# higs_bc_eee.net
KiCad netlist of a schematic drawn in EAGLE
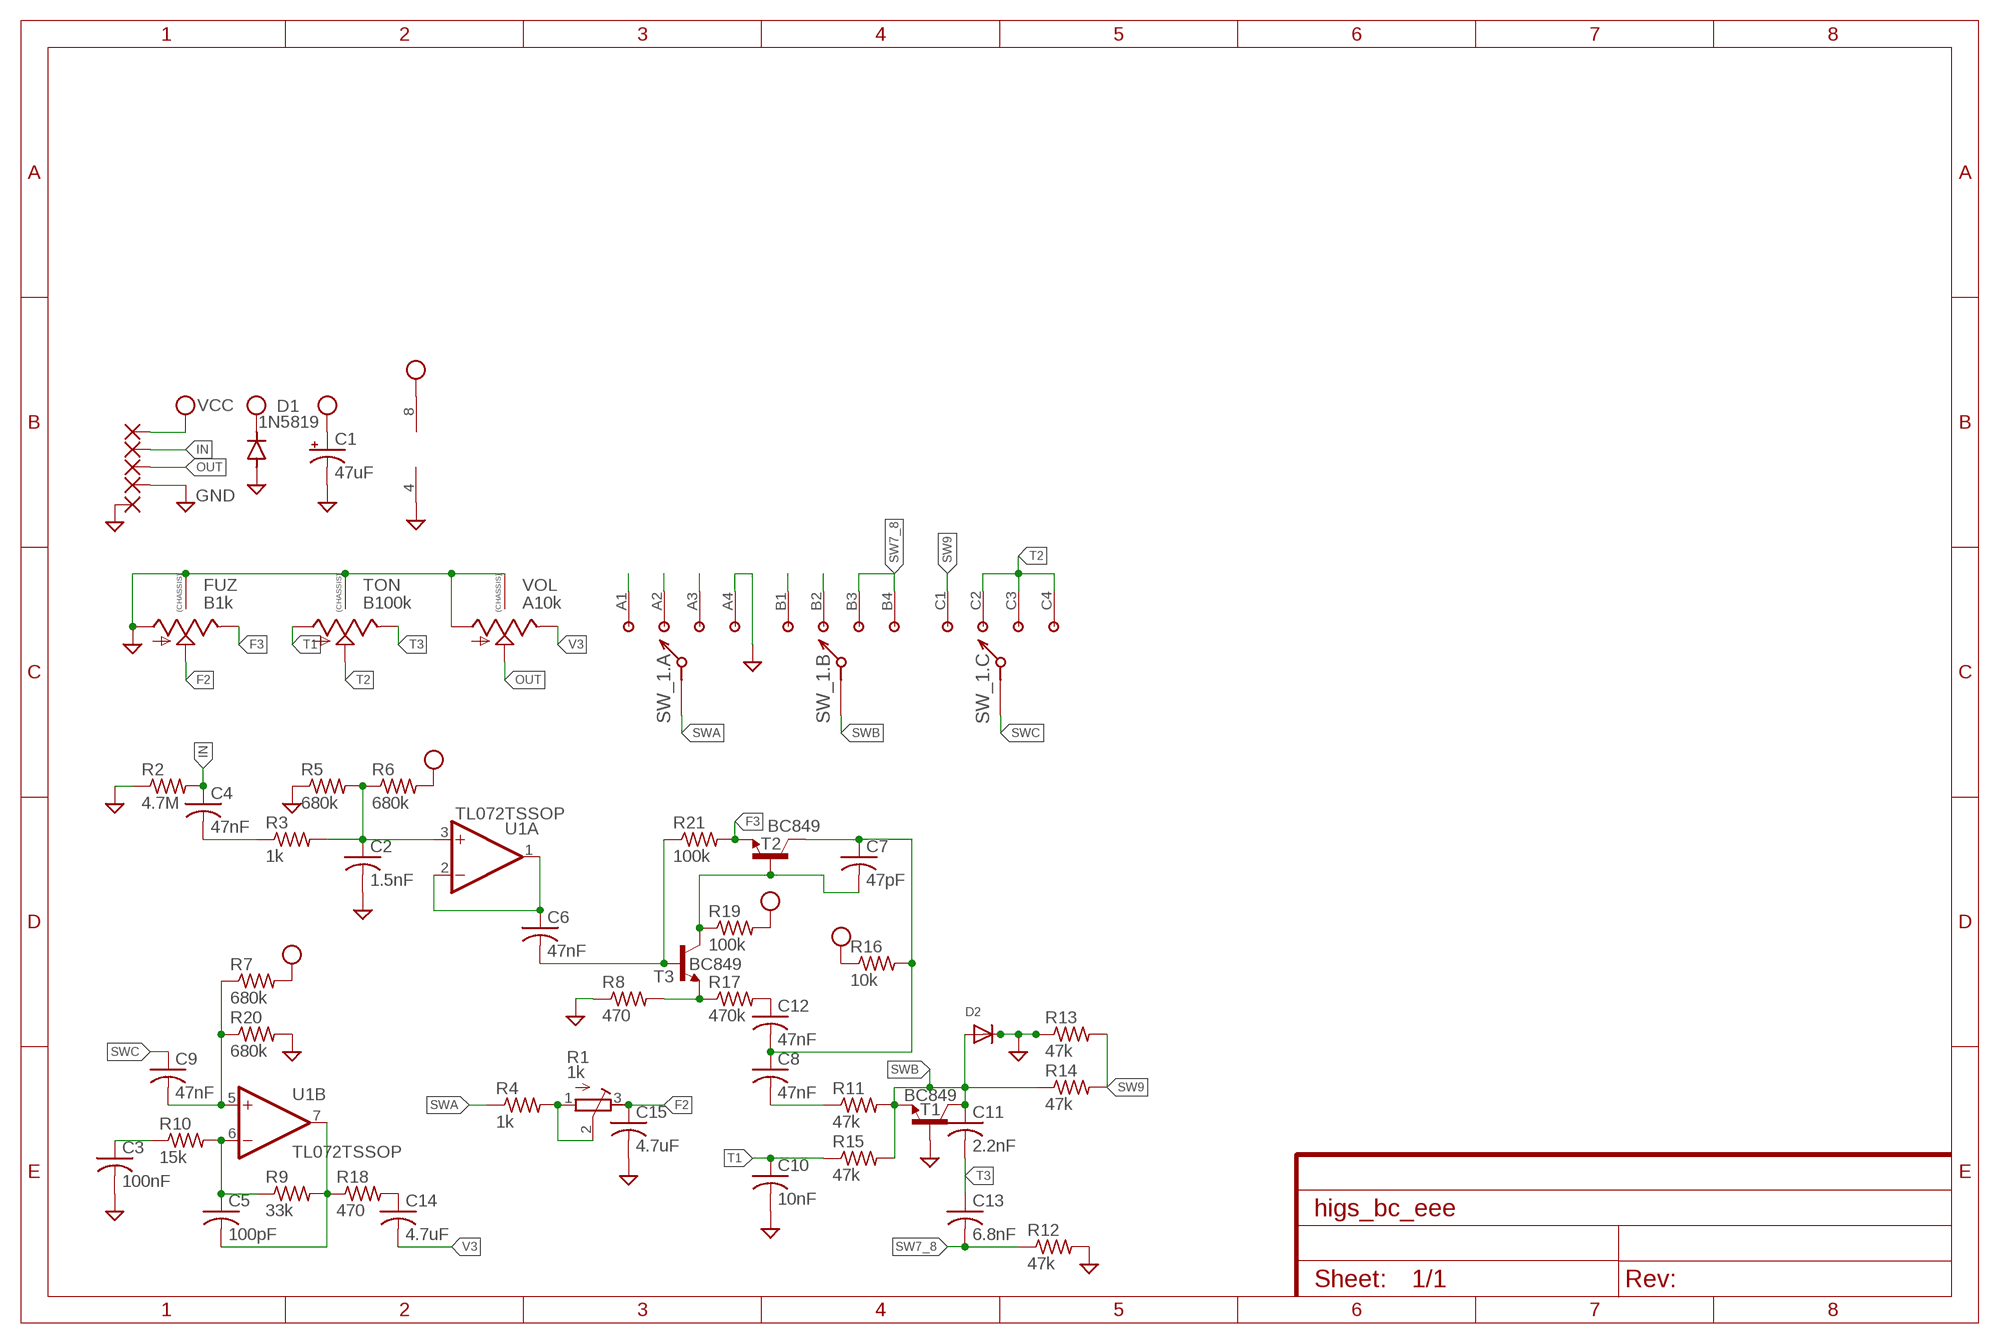
[diagram p0: schematic, sheet 1]

(export (version "E")
  (design (tool "Eeschema 10.0.6"))
  (components
    (comp (ref "C1")
      (value "47uF")
      (footprint "eagle-import:CPOL-RADIAL-2.5MM-6.5MM")
      (libsource (lib "eagle-import") (part "100UF-POLAR-RADIAL-2.5MM-25V-20%"))
    )
    (comp (ref "C2")
      (value "1.5nF")
      (footprint "eagle-import:C0603")
      (libsource (lib "eagle-import") (part "C-USC0603"))
    )
    (comp (ref "C3")
      (value "100nF")
      (footprint "eagle-import:C0603")
      (libsource (lib "eagle-import") (part "C-USC0603"))
    )
    (comp (ref "C4")
      (value "47nF")
      (footprint "eagle-import:C0603")
      (libsource (lib "eagle-import") (part "C-USC0603"))
    )
    (comp (ref "C5")
      (value "100pF")
      (footprint "eagle-import:C0603")
      (libsource (lib "eagle-import") (part "C-USC0603"))
    )
    (comp (ref "C6")
      (value "47nF")
      (footprint "eagle-import:C0603")
      (libsource (lib "eagle-import") (part "C-USC0603"))
    )
    (comp (ref "C7")
      (value "47pF")
      (footprint "eagle-import:C0603")
      (libsource (lib "eagle-import") (part "C-USC0603"))
    )
    (comp (ref "C8")
      (value "47nF")
      (footprint "eagle-import:C0603")
      (libsource (lib "eagle-import") (part "C-USC0603"))
    )
    (comp (ref "C9")
      (value "47nF")
      (footprint "eagle-import:C0603")
      (libsource (lib "eagle-import") (part "C-USC0603"))
    )
    (comp (ref "C10")
      (value "10nF")
      (footprint "eagle-import:C0603")
      (libsource (lib "eagle-import") (part "C-USC0603"))
    )
    (comp (ref "C11")
      (value "2.2nF")
      (footprint "eagle-import:C0603")
      (libsource (lib "eagle-import") (part "C-USC0603"))
    )
    (comp (ref "C12")
      (value "47nF")
      (footprint "eagle-import:C0603")
      (libsource (lib "eagle-import") (part "C-USC0603"))
    )
    (comp (ref "C13")
      (value "6.8nF")
      (footprint "eagle-import:C0603")
      (libsource (lib "eagle-import") (part "C-USC0603"))
    )
    (comp (ref "C14")
      (value "4.7uF")
      (footprint "eagle-import:C1206")
      (libsource (lib "eagle-import") (part "C-USC1206"))
    )
    (comp (ref "C15")
      (value "4.7uF")
      (footprint "eagle-import:C1206")
      (libsource (lib "eagle-import") (part "C-USC1206"))
    )
    (comp (ref "D1")
      (value "1N5819")
      (footprint "eagle-import:SOD123")
      (libsource (lib "eagle-import") (part "DIODE-SOD123"))
    )
    (comp (ref "D2")
      (value "DIODESOD-123")
      (footprint "eagle-import:SOD-123")
      (libsource (lib "eagle-import") (part "DIODESOD-123"))
    )
    (comp (ref "FUZ")
      (value "B1k")
      (footprint "eagle-import:9MM_SNAP-IN_POT")
      (libsource (lib "eagle-import") (part "9MM_SNAP-IN_POT_CHASSIS"))
    )
    (comp (ref "PAD1")
      (value "1,6/0,8")
      (footprint "eagle-import:1,6_0,8")
      (libsource (lib "eagle-import") (part "1,6/0,8"))
    )
    (comp (ref "PAD2")
      (value "1,6/0,8")
      (footprint "eagle-import:1,6_0,8")
      (libsource (lib "eagle-import") (part "1,6/0,8"))
    )
    (comp (ref "PAD3")
      (value "1,6/0,8")
      (footprint "eagle-import:1,6_0,8")
      (libsource (lib "eagle-import") (part "1,6/0,8"))
    )
    (comp (ref "PAD4")
      (value "1,6/0,8")
      (footprint "eagle-import:1,6_0,8")
      (libsource (lib "eagle-import") (part "1,6/0,8"))
    )
    (comp (ref "PAD5")
      (value "1,6/0,8")
      (footprint "eagle-import:1,6_0,8")
      (libsource (lib "eagle-import") (part "1,6/0,8"))
    )
    (comp (ref "R1")
      (value "1k")
      (footprint "eagle-import:RTRIM3224W")
      (libsource (lib "eagle-import") (part "R-TRIMM3224W"))
    )
    (comp (ref "R2")
      (value "4.7M")
      (footprint "eagle-import:R0603")
      (libsource (lib "eagle-import") (part "R-US_R0603"))
    )
    (comp (ref "R3")
      (value "1k")
      (footprint "eagle-import:R0603")
      (libsource (lib "eagle-import") (part "R-US_R0603"))
    )
    (comp (ref "R4")
      (value "1k")
      (footprint "eagle-import:R0603")
      (libsource (lib "eagle-import") (part "R-US_R0603"))
    )
    (comp (ref "R5")
      (value "680k")
      (footprint "eagle-import:R0603")
      (libsource (lib "eagle-import") (part "R-US_R0603"))
    )
    (comp (ref "R6")
      (value "680k")
      (footprint "eagle-import:R0603")
      (libsource (lib "eagle-import") (part "R-US_R0603"))
    )
    (comp (ref "R7")
      (value "680k")
      (footprint "eagle-import:R0603")
      (libsource (lib "eagle-import") (part "R-US_R0603"))
    )
    (comp (ref "R8")
      (value "470")
      (footprint "eagle-import:R0603")
      (libsource (lib "eagle-import") (part "R-US_R0603"))
    )
    (comp (ref "R9")
      (value "33k")
      (footprint "eagle-import:R0603")
      (libsource (lib "eagle-import") (part "R-US_R0603"))
    )
    (comp (ref "R10")
      (value "15k")
      (footprint "eagle-import:R0603")
      (libsource (lib "eagle-import") (part "R-US_R0603"))
    )
    (comp (ref "R11")
      (value "47k")
      (footprint "eagle-import:R0603")
      (libsource (lib "eagle-import") (part "R-US_R0603"))
    )
    (comp (ref "R12")
      (value "47k")
      (footprint "eagle-import:R0603")
      (libsource (lib "eagle-import") (part "R-US_R0603"))
    )
    (comp (ref "R13")
      (value "47k")
      (footprint "eagle-import:R0603")
      (libsource (lib "eagle-import") (part "R-US_R0603"))
    )
    (comp (ref "R14")
      (value "47k")
      (footprint "eagle-import:R0603")
      (libsource (lib "eagle-import") (part "R-US_R0603"))
    )
    (comp (ref "R15")
      (value "47k")
      (footprint "eagle-import:R0603")
      (libsource (lib "eagle-import") (part "R-US_R0603"))
    )
    (comp (ref "R16")
      (value "10k")
      (footprint "eagle-import:R0603")
      (libsource (lib "eagle-import") (part "R-US_R0603"))
    )
    (comp (ref "R17")
      (value "470k")
      (footprint "eagle-import:R0603")
      (libsource (lib "eagle-import") (part "R-US_R0603"))
    )
    (comp (ref "R18")
      (value "470")
      (footprint "eagle-import:R0603")
      (libsource (lib "eagle-import") (part "R-US_R0603"))
    )
    (comp (ref "R19")
      (value "100k")
      (footprint "eagle-import:R0603")
      (libsource (lib "eagle-import") (part "R-US_R0603"))
    )
    (comp (ref "R20")
      (value "680k")
      (footprint "eagle-import:R0603")
      (libsource (lib "eagle-import") (part "R-US_R0603"))
    )
    (comp (ref "R21")
      (value "100k")
      (footprint "eagle-import:R0603")
      (libsource (lib "eagle-import") (part "R-US_R0603"))
    )
    (comp (ref "SW_1")
      (value "3P4T")
      (footprint "eagle-import:3P4T")
      (libsource (lib "eagle-import") (part "3P4T"))
    )
    (comp (ref "T1")
      (value "BC849")
      (footprint "eagle-import:SOT23-BEC")
      (libsource (lib "eagle-import") (part "-NPN-SOT23-BECBC849"))
    )
    (comp (ref "T2")
      (value "BC849")
      (footprint "eagle-import:SOT23-BEC")
      (libsource (lib "eagle-import") (part "-NPN-SOT23-BECBC849"))
    )
    (comp (ref "T3")
      (value "BC849")
      (footprint "eagle-import:SOT23-BEC")
      (libsource (lib "eagle-import") (part "-NPN-SOT23-BECBC849"))
    )
    (comp (ref "TON")
      (value "B100k")
      (footprint "eagle-import:9MM_SNAP-IN_POT")
      (libsource (lib "eagle-import") (part "9MM_SNAP-IN_POT_CHASSIS"))
    )
    (comp (ref "U1")
      (value "TL072TSSOP")
      (footprint "eagle-import:TSSOP-8")
      (libsource (lib "eagle-import") (part "TL072TSSOP"))
    )
    (comp (ref "VOL")
      (value "A10k")
      (footprint "eagle-import:9MM_SNAP-IN_POT")
      (libsource (lib "eagle-import") (part "9MM_SNAP-IN_POT_CHASSIS"))
    )
  )
  (nets
    (net (code "1") (name "F2") (class "Default")
      (node (ref "C15") (pin "1") (pinfunction "1_1") (pintype "passive"))
      (node (ref "FUZ") (pin "2") (pinfunction "S_2") (pintype "passive"))
      (node (ref "R1") (pin "3") (pinfunction "E_3") (pintype "passive"))
    )
    (net (code "2") (name "F3") (class "Default")
      (node (ref "FUZ") (pin "3") (pinfunction "E_3") (pintype "passive"))
      (node (ref "R21") (pin "2") (pinfunction "2_2") (pintype "passive"))
      (node (ref "T2") (pin "E") (pinfunction "E_E") (pintype "passive"))
    )
    (net (code "3") (name "GND") (class "Default")
      (node (ref "C1") (pin "2") (pinfunction "-_2") (pintype "passive"))
      (node (ref "C10") (pin "2") (pinfunction "2_2") (pintype "passive"))
      (node (ref "C15") (pin "2") (pinfunction "2_2") (pintype "passive"))
      (node (ref "C2") (pin "2") (pinfunction "2_2") (pintype "passive"))
      (node (ref "C3") (pin "2") (pinfunction "2_2") (pintype "passive"))
      (node (ref "D1") (pin "A") (pinfunction "A_A") (pintype "passive"))
      (node (ref "D2") (pin "C") (pinfunction "C_C") (pintype "passive"))
      (node (ref "FUZ") (pin "1") (pinfunction "A_1") (pintype "passive"))
      (node (ref "FUZ") (pin "CHASSIS1") (pinfunction "P$1_CHASSIS1") (pintype "passive"))
      (node (ref "FUZ") (pin "CHASSIS2") (pinfunction "P$1_CHASSIS2") (pintype "passive"))
      (node (ref "PAD4") (pin "1") (pinfunction "P_1") (pintype "passive"))
      (node (ref "PAD5") (pin "1") (pinfunction "P_1") (pintype "passive"))
      (node (ref "R12") (pin "2") (pinfunction "2_2") (pintype "passive"))
      (node (ref "R13") (pin "1") (pinfunction "1_1") (pintype "passive"))
      (node (ref "R2") (pin "1") (pinfunction "1_1") (pintype "passive"))
      (node (ref "R20") (pin "2") (pinfunction "2_2") (pintype "passive"))
      (node (ref "R5") (pin "1") (pinfunction "1_1") (pintype "passive"))
      (node (ref "R8") (pin "1") (pinfunction "1_1") (pintype "passive"))
      (node (ref "SW_1") (pin "A4") (pinfunction "4_A4") (pintype "bidirectional"))
      (node (ref "T1") (pin "B") (pinfunction "B_B") (pintype "passive"))
      (node (ref "TON") (pin "CHASSIS1") (pinfunction "P$1_CHASSIS1") (pintype "passive"))
      (node (ref "TON") (pin "CHASSIS2") (pinfunction "P$1_CHASSIS2") (pintype "passive"))
      (node (ref "U1") (pin "4") (pinfunction "V-_4") (pintype "power_in"))
      (node (ref "VOL") (pin "1") (pinfunction "A_1") (pintype "passive"))
      (node (ref "VOL") (pin "CHASSIS1") (pinfunction "P$1_CHASSIS1") (pintype "passive"))
      (node (ref "VOL") (pin "CHASSIS2") (pinfunction "P$1_CHASSIS2") (pintype "passive"))
    )
    (net (code "4") (name "IN") (class "Default")
      (node (ref "C4") (pin "1") (pinfunction "1_1") (pintype "passive"))
      (node (ref "PAD2") (pin "1") (pinfunction "P_1") (pintype "passive"))
      (node (ref "R2") (pin "2") (pinfunction "2_2") (pintype "passive"))
    )
    (net (code "5") (name "Net-(C3-Pad1)") (class "Default")
      (node (ref "C3") (pin "1") (pinfunction "1_1") (pintype "passive"))
      (node (ref "R10") (pin "1") (pinfunction "1_1") (pintype "passive"))
    )
    (net (code "6") (name "Net-(C4-Pad2)") (class "Default")
      (node (ref "C4") (pin "2") (pinfunction "2_2") (pintype "passive"))
      (node (ref "R3") (pin "1") (pinfunction "1_1") (pintype "passive"))
    )
    (net (code "7") (name "Net-(C6-Pad2)") (class "Default")
      (node (ref "C6") (pin "2") (pinfunction "2_2") (pintype "passive"))
      (node (ref "R21") (pin "1") (pinfunction "1_1") (pintype "passive"))
      (node (ref "T3") (pin "B") (pinfunction "B_B") (pintype "passive"))
    )
    (net (code "8") (name "Net-(C7-Pad2)") (class "Default")
      (node (ref "C7") (pin "2") (pinfunction "2_2") (pintype "passive"))
      (node (ref "R19") (pin "1") (pinfunction "1_1") (pintype "passive"))
      (node (ref "T2") (pin "B") (pinfunction "B_B") (pintype "passive"))
      (node (ref "T3") (pin "C") (pinfunction "C_C") (pintype "passive"))
    )
    (net (code "9") (name "Net-(C8-Pad2)") (class "Default")
      (node (ref "C8") (pin "2") (pinfunction "2_2") (pintype "passive"))
      (node (ref "R11") (pin "1") (pinfunction "1_1") (pintype "passive"))
    )
    (net (code "10") (name "Net-(C12-Pad1)") (class "Default")
      (node (ref "C12") (pin "1") (pinfunction "1_1") (pintype "passive"))
      (node (ref "R17") (pin "2") (pinfunction "2_2") (pintype "passive"))
    )
    (net (code "11") (name "Net-(C12-Pad2)") (class "Default")
      (node (ref "C12") (pin "2") (pinfunction "2_2") (pintype "passive"))
      (node (ref "C7") (pin "1") (pinfunction "1_1") (pintype "passive"))
      (node (ref "C8") (pin "1") (pinfunction "1_1") (pintype "passive"))
      (node (ref "R16") (pin "2") (pinfunction "2_2") (pintype "passive"))
      (node (ref "T2") (pin "C") (pinfunction "C_C") (pintype "passive"))
    )
    (net (code "12") (name "Net-(C14-Pad1)") (class "Default")
      (node (ref "C14") (pin "1") (pinfunction "1_1") (pintype "passive"))
      (node (ref "R18") (pin "2") (pinfunction "2_2") (pintype "passive"))
    )
    (net (code "13") (name "Net-(R1-A)") (class "Default")
      (node (ref "R1") (pin "1") (pinfunction "A_1") (pintype "passive"))
      (node (ref "R1") (pin "2") (pinfunction "S_2") (pintype "passive"))
      (node (ref "R4") (pin "2") (pinfunction "2_2") (pintype "passive"))
    )
    (net (code "14") (name "Net-(R17-Pad1)") (class "Default")
      (node (ref "R17") (pin "1") (pinfunction "1_1") (pintype "passive"))
      (node (ref "R8") (pin "2") (pinfunction "2_2") (pintype "passive"))
      (node (ref "T3") (pin "E") (pinfunction "E_E") (pintype "passive"))
    )
    (net (code "15") (name "Net-(U1A-+IN)") (class "Default")
      (node (ref "C2") (pin "1") (pinfunction "1_1") (pintype "passive"))
      (node (ref "R3") (pin "2") (pinfunction "2_2") (pintype "passive"))
      (node (ref "R5") (pin "2") (pinfunction "2_2") (pintype "passive"))
      (node (ref "R6") (pin "1") (pinfunction "1_1") (pintype "passive"))
      (node (ref "U1") (pin "3") (pinfunction "+IN_3") (pintype "input"))
    )
    (net (code "16") (name "Net-(U1A--IN)") (class "Default")
      (node (ref "C6") (pin "1") (pinfunction "1_1") (pintype "passive"))
      (node (ref "U1") (pin "1") (pinfunction "OUT_1") (pintype "output"))
      (node (ref "U1") (pin "2") (pinfunction "-IN_2") (pintype "input"))
    )
    (net (code "17") (name "Net-(U1B-+IN)") (class "Default")
      (node (ref "C9") (pin "2") (pinfunction "2_2") (pintype "passive"))
      (node (ref "R20") (pin "1") (pinfunction "1_1") (pintype "passive"))
      (node (ref "R7") (pin "1") (pinfunction "1_1") (pintype "passive"))
      (node (ref "U1") (pin "5") (pinfunction "+IN_5") (pintype "input"))
    )
    (net (code "18") (name "Net-(U1B--IN)") (class "Default")
      (node (ref "C5") (pin "1") (pinfunction "1_1") (pintype "passive"))
      (node (ref "R10") (pin "2") (pinfunction "2_2") (pintype "passive"))
      (node (ref "R9") (pin "1") (pinfunction "1_1") (pintype "passive"))
      (node (ref "U1") (pin "6") (pinfunction "-IN_6") (pintype "input"))
    )
    (net (code "19") (name "Net-(U1B-OUT)") (class "Default")
      (node (ref "C5") (pin "2") (pinfunction "2_2") (pintype "passive"))
      (node (ref "R18") (pin "1") (pinfunction "1_1") (pintype "passive"))
      (node (ref "R9") (pin "2") (pinfunction "2_2") (pintype "passive"))
      (node (ref "U1") (pin "7") (pinfunction "OUT_7") (pintype "output"))
    )
    (net (code "20") (name "OUT") (class "Default")
      (node (ref "PAD3") (pin "1") (pinfunction "P_1") (pintype "passive"))
      (node (ref "VOL") (pin "2") (pinfunction "S_2") (pintype "passive"))
    )
    (net (code "21") (name "SW7_8") (class "Default")
      (node (ref "C13") (pin "2") (pinfunction "2_2") (pintype "passive"))
      (node (ref "R12") (pin "1") (pinfunction "1_1") (pintype "passive"))
      (node (ref "SW_1") (pin "B3") (pinfunction "3_B3") (pintype "bidirectional"))
      (node (ref "SW_1") (pin "B4") (pinfunction "4_B4") (pintype "bidirectional"))
    )
    (net (code "22") (name "SW9") (class "Default")
      (node (ref "R13") (pin "2") (pinfunction "2_2") (pintype "passive"))
      (node (ref "R14") (pin "2") (pinfunction "2_2") (pintype "passive"))
      (node (ref "SW_1") (pin "C1") (pinfunction "1_C1") (pintype "bidirectional"))
    )
    (net (code "23") (name "SWA") (class "Default")
      (node (ref "R4") (pin "1") (pinfunction "1_1") (pintype "passive"))
      (node (ref "SW_1") (pin "A") (pinfunction "A_A") (pintype "bidirectional"))
    )
    (net (code "24") (name "SWB") (class "Default")
      (node (ref "C11") (pin "1") (pinfunction "1_1") (pintype "passive"))
      (node (ref "D2") (pin "A") (pinfunction "A_A") (pintype "passive"))
      (node (ref "R11") (pin "2") (pinfunction "2_2") (pintype "passive"))
      (node (ref "R14") (pin "1") (pinfunction "1_1") (pintype "passive"))
      (node (ref "R15") (pin "2") (pinfunction "2_2") (pintype "passive"))
      (node (ref "SW_1") (pin "B") (pinfunction "A_B") (pintype "bidirectional"))
      (node (ref "T1") (pin "C") (pinfunction "C_C") (pintype "passive"))
      (node (ref "T1") (pin "E") (pinfunction "E_E") (pintype "passive"))
    )
    (net (code "25") (name "SWC") (class "Default")
      (node (ref "C9") (pin "1") (pinfunction "1_1") (pintype "passive"))
      (node (ref "SW_1") (pin "C") (pinfunction "A_C") (pintype "bidirectional"))
    )
    (net (code "26") (name "T1") (class "Default")
      (node (ref "C10") (pin "1") (pinfunction "1_1") (pintype "passive"))
      (node (ref "R15") (pin "1") (pinfunction "1_1") (pintype "passive"))
      (node (ref "TON") (pin "1") (pinfunction "A_1") (pintype "passive"))
    )
    (net (code "27") (name "T2") (class "Default")
      (node (ref "SW_1") (pin "C2") (pinfunction "2_C2") (pintype "bidirectional"))
      (node (ref "SW_1") (pin "C3") (pinfunction "3_C3") (pintype "bidirectional"))
      (node (ref "SW_1") (pin "C4") (pinfunction "4_C4") (pintype "bidirectional"))
      (node (ref "TON") (pin "2") (pinfunction "S_2") (pintype "passive"))
    )
    (net (code "28") (name "T3") (class "Default")
      (node (ref "C11") (pin "2") (pinfunction "2_2") (pintype "passive"))
      (node (ref "C13") (pin "1") (pinfunction "1_1") (pintype "passive"))
      (node (ref "TON") (pin "3") (pinfunction "E_3") (pintype "passive"))
    )
    (net (code "29") (name "V3") (class "Default")
      (node (ref "C14") (pin "2") (pinfunction "2_2") (pintype "passive"))
      (node (ref "VOL") (pin "3") (pinfunction "E_3") (pintype "passive"))
    )
    (net (code "30") (name "VCC") (class "Default")
      (node (ref "C1") (pin "1") (pinfunction "+_1") (pintype "passive"))
      (node (ref "D1") (pin "C") (pinfunction "C_C") (pintype "passive"))
      (node (ref "PAD1") (pin "1") (pinfunction "P_1") (pintype "passive"))
      (node (ref "R16") (pin "1") (pinfunction "1_1") (pintype "passive"))
      (node (ref "R19") (pin "2") (pinfunction "2_2") (pintype "passive"))
      (node (ref "R6") (pin "2") (pinfunction "2_2") (pintype "passive"))
      (node (ref "R7") (pin "2") (pinfunction "2_2") (pintype "passive"))
      (node (ref "U1") (pin "8") (pinfunction "V+_8") (pintype "power_in"))
    )
    (net (code "31") (name "unconnected-(SW_1A-1-PadA1)") (class "Default")
      (node (ref "SW_1") (pin "A1") (pinfunction "1_A1") (pintype "bidirectional"))
    )
    (net (code "32") (name "unconnected-(SW_1A-2-PadA2)") (class "Default")
      (node (ref "SW_1") (pin "A2") (pinfunction "2_A2") (pintype "bidirectional"))
    )
    (net (code "33") (name "unconnected-(SW_1A-3-PadA3)") (class "Default")
      (node (ref "SW_1") (pin "A3") (pinfunction "3_A3") (pintype "bidirectional"))
    )
    (net (code "34") (name "unconnected-(SW_1B-1-PadB1)") (class "Default")
      (node (ref "SW_1") (pin "B1") (pinfunction "1_B1") (pintype "bidirectional"))
    )
    (net (code "35") (name "unconnected-(SW_1B-2-PadB2)") (class "Default")
      (node (ref "SW_1") (pin "B2") (pinfunction "2_B2") (pintype "bidirectional"))
    )
  )
)
